# Demo.net
KiCad netlist of a schematic drawn in EAGLE
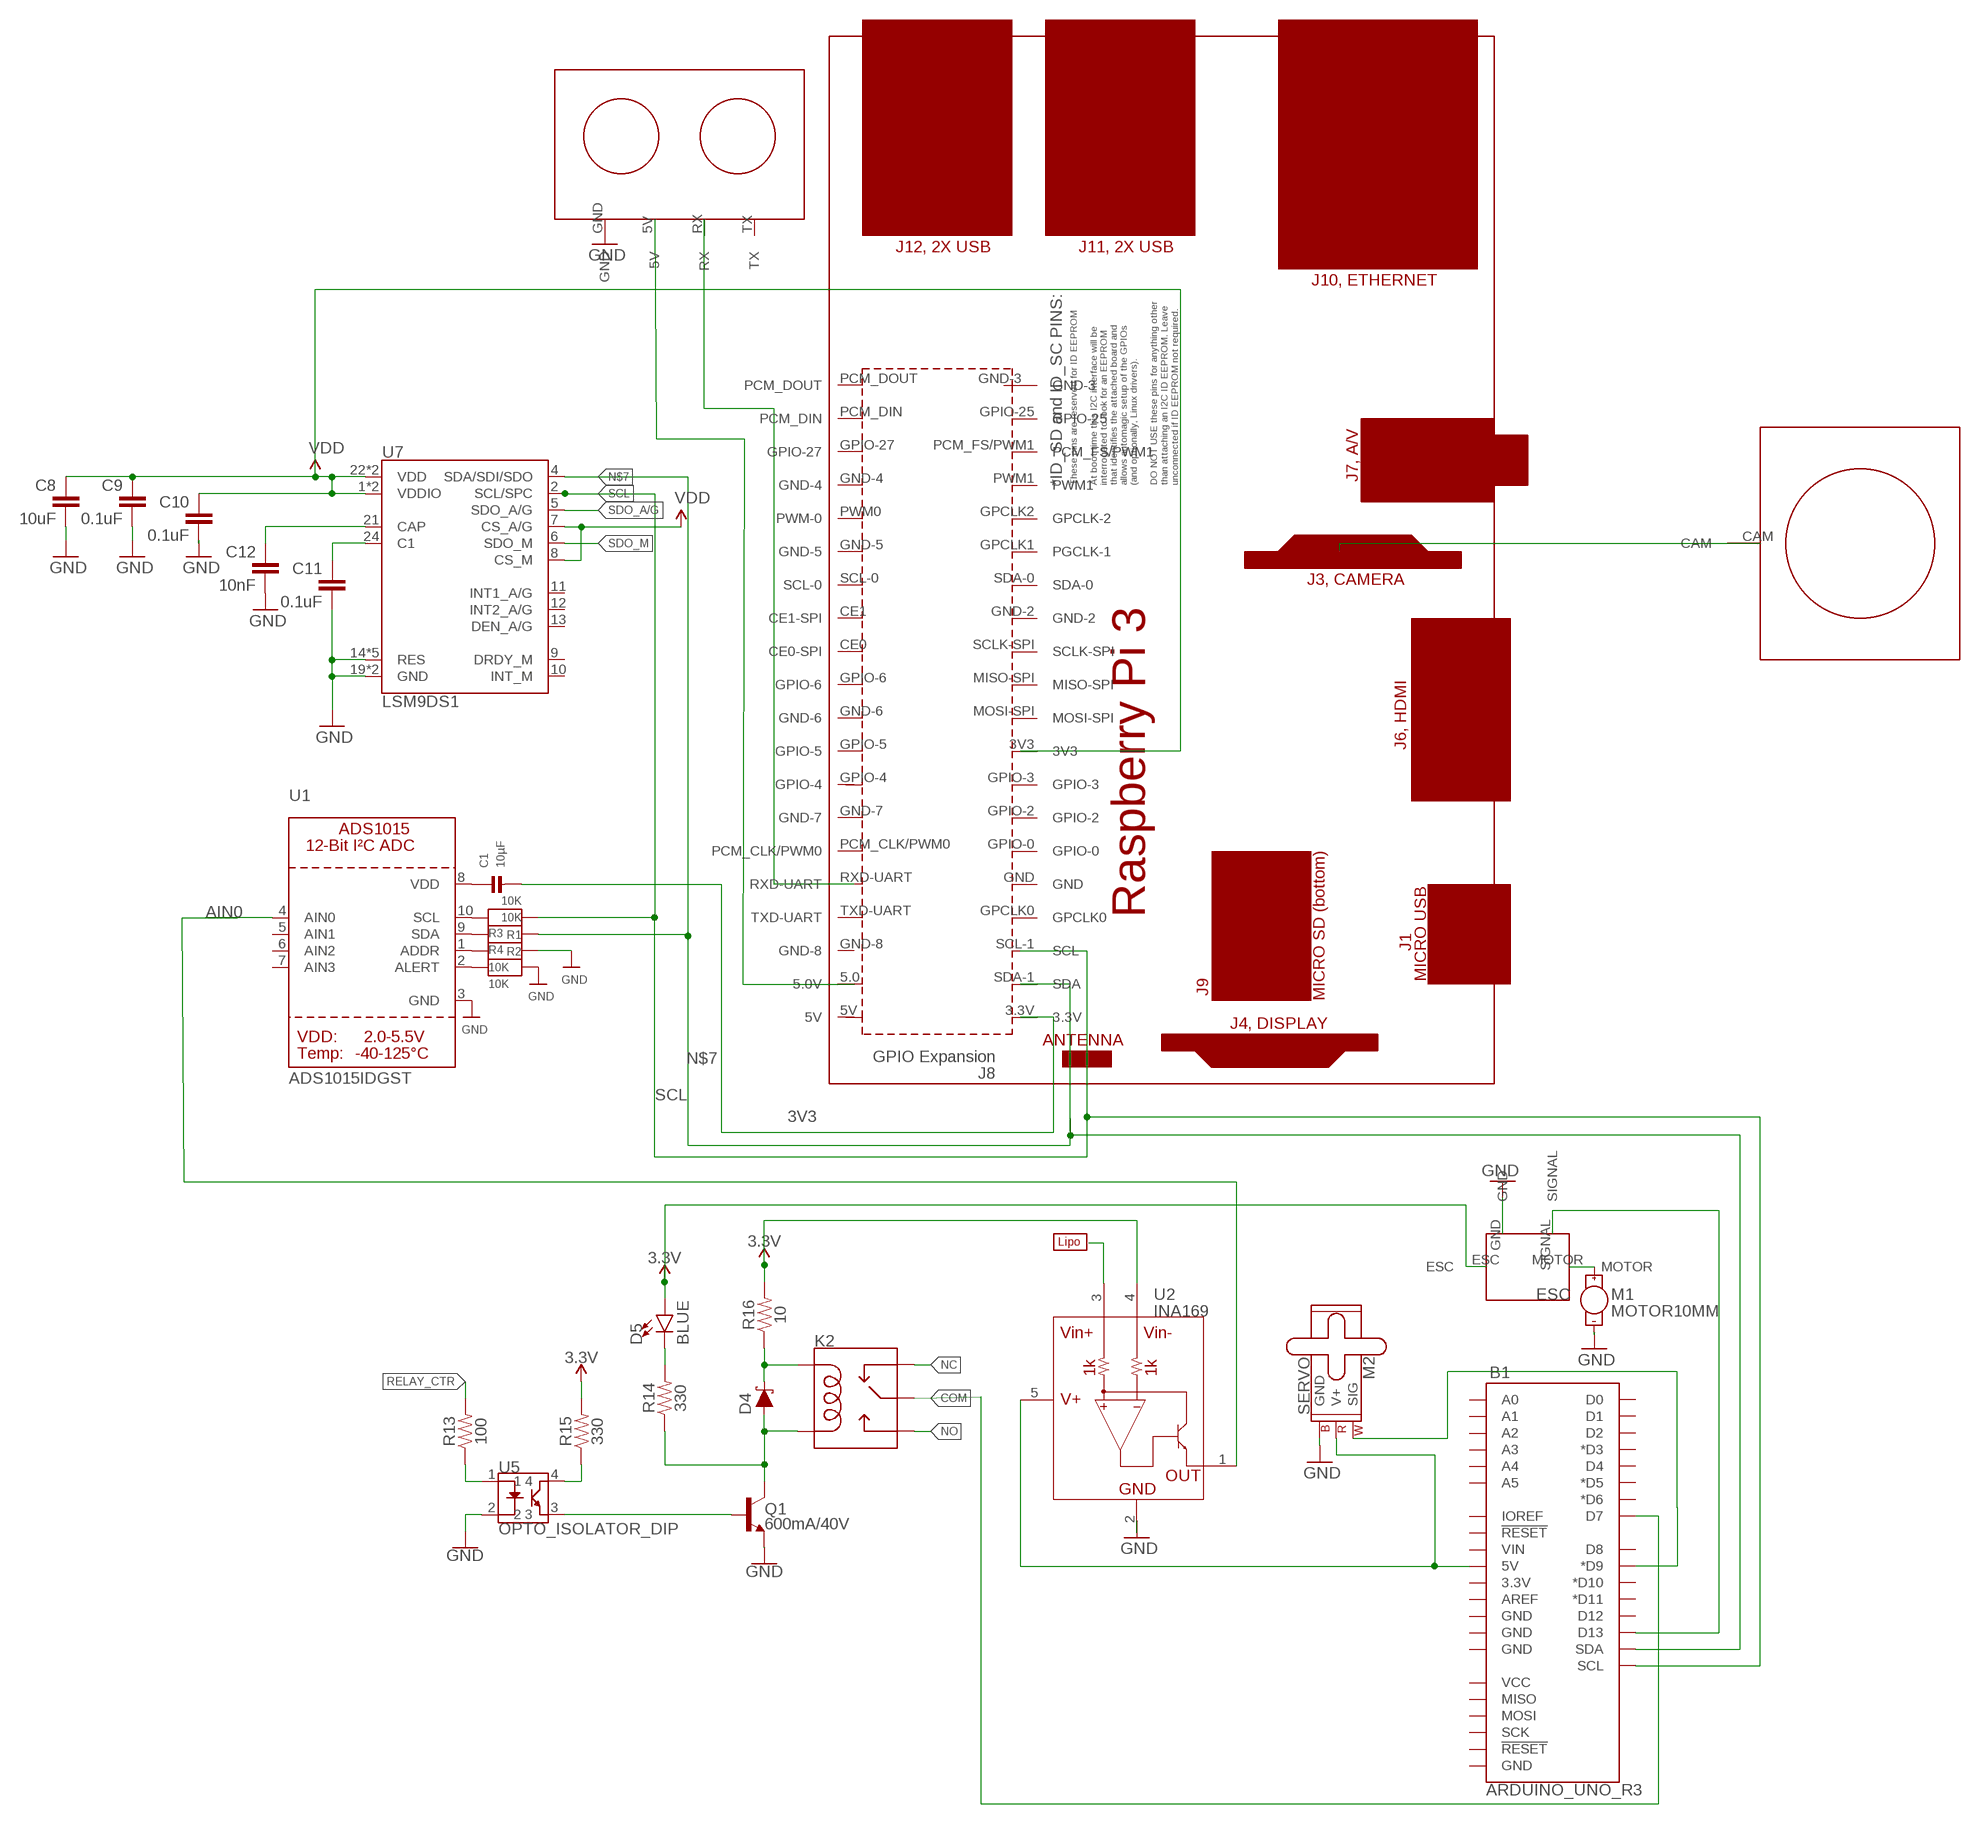
[diagram p0: schematic, sheet 1]

(export (version "E")
  (design (tool "Eeschema 10.0.6"))
  (components
    (comp (ref "B1")
      (value "ARDUINO_UNO_R3")
      (footprint "eagle-import:ARDUINO_R3")
      (libsource (lib "eagle-import") (part "ARDUINO_UNO_R3"))
    )
    (comp (ref "BT1")
      (value "LIPO-OUTLINE1100")
      (footprint "eagle-import:LIPO-1000")
      (libsource (lib "eagle-import") (part "LIPO-OUTLINE1100"))
    )
    (comp (ref "C1")
      (value "10µF")
      (footprint "eagle-import:0805")
      (libsource (lib "eagle-import") (part "CAP_CERAMIC0805"))
    )
    (comp (ref "C8")
      (value "10uF")
      (footprint "eagle-import:0603-CAP")
      (libsource (lib "eagle-import") (part "10UF-6.3V-20%(0603)"))
    )
    (comp (ref "C9")
      (value "0.1uF")
      (footprint "eagle-import:0603-CAP")
      (libsource (lib "eagle-import") (part "0.1UF-25V(+80/-20%)(0603)"))
    )
    (comp (ref "C10")
      (value "0.1uF")
      (footprint "eagle-import:0603-CAP")
      (libsource (lib "eagle-import") (part "0.1UF-25V(+80/-20%)(0603)"))
    )
    (comp (ref "C11")
      (value "0.1uF")
      (footprint "eagle-import:0603-CAP")
      (libsource (lib "eagle-import") (part "0.1UF-25V(+80/-20%)(0603)"))
    )
    (comp (ref "C12")
      (value "10nF")
      (footprint "eagle-import:0603-CAP")
      (libsource (lib "eagle-import") (part "10NF/10000PF-50V-10%(0603)"))
    )
    (comp (ref "D4")
      (value "1A/23V/620mV")
      (footprint "eagle-import:SOD-323")
      (libsource (lib "eagle-import") (part "DIODE-SCHOTTKY-BAT20J"))
    )
    (comp (ref "D5")
      (value "BLUE")
      (footprint "eagle-import:LED-0603")
      (libsource (lib "eagle-import") (part "LED-BLUE0603"))
    )
    (comp (ref "K2")
      (value "RELAY_SPDT_1C")
      (footprint "eagle-import:RELAY_SPDT_1C")
      (libsource (lib "eagle-import") (part "RELAY_SPDT_1C"))
    )
    (comp (ref "M1")
      (value "MOTOR10MM")
      (footprint "eagle-import:VIBE-MOTOR-10MM")
      (libsource (lib "eagle-import") (part "MOTOR10MM"))
    )
    (comp (ref "M2")
      (value "SERVO")
      (footprint "eagle-import:1X03")
      (libsource (lib "eagle-import") (part "SERVO"))
    )
    (comp (ref "Q1")
      (value "600mA/40V")
      (footprint "eagle-import:SOT23-3")
      (libsource (lib "eagle-import") (part "TRANS_NPN-MMBT2222AL"))
    )
    (comp (ref "R1")
      (value "10K")
      (footprint "eagle-import:0805")
      (libsource (lib "eagle-import") (part "RESISTOR0805"))
    )
    (comp (ref "R2")
      (value "10K")
      (footprint "eagle-import:0805")
      (libsource (lib "eagle-import") (part "RESISTOR0805"))
    )
    (comp (ref "R3")
      (value "10K")
      (footprint "eagle-import:0805")
      (libsource (lib "eagle-import") (part "RESISTOR0805"))
    )
    (comp (ref "R4")
      (value "10K")
      (footprint "eagle-import:0805")
      (libsource (lib "eagle-import") (part "RESISTOR0805"))
    )
    (comp (ref "R13")
      (value "100")
      (footprint "eagle-import:0603")
      (libsource (lib "eagle-import") (part "100OHM-0603-1/4W-5%"))
    )
    (comp (ref "R14")
      (value "330")
      (footprint "eagle-import:0603")
      (libsource (lib "eagle-import") (part "300OHM-0603-1/10W-1%"))
    )
    (comp (ref "R15")
      (value "330")
      (footprint "eagle-import:0603")
      (libsource (lib "eagle-import") (part "330OHM-0603-1/10W-1%"))
    )
    (comp (ref "R16")
      (value "10")
      (footprint "eagle-import:0603")
      (libsource (lib "eagle-import") (part "47KOHM-0603-1/10W-1%"))
    )
    (comp (ref "RPI1")
      (value "RPI3")
      (footprint "eagle-import:RPI")
      (libsource (lib "eagle-import") (part "RPI3"))
    )
    (comp (ref "U$1")
      (value "ESC")
      (footprint "eagle-import:ESC")
      (libsource (lib "eagle-import") (part "ESC"))
    )
    (comp (ref "U$3")
      (value "CAMERA")
      (footprint "eagle-import:CAMERA")
      (libsource (lib "eagle-import") (part "CAMERA"))
    )
    (comp (ref "U$4")
      (value "LIDAR")
      (footprint "eagle-import:LIDAR")
      (libsource (lib "eagle-import") (part "LIDAR"))
    )
    (comp (ref "U1")
      (value "ADS1015IDGST")
      (footprint "eagle-import:MSOP10")
      (libsource (lib "eagle-import") (part "ADC_ADS1015"))
    )
    (comp (ref "U2")
      (value "INA169")
      (footprint "eagle-import:SOT23-5")
      (libsource (lib "eagle-import") (part "INA169"))
    )
    (comp (ref "U5")
      (value "OPTO_ISOLATOR_DIP")
      (footprint "eagle-import:4PIN_DIP")
      (libsource (lib "eagle-import") (part "OPTO_ISOLATOR_DIP"))
    )
    (comp (ref "U7")
      (value "LSM9DS1")
      (footprint "eagle-import:LGA24-8X4")
      (libsource (lib "eagle-import") (part "LSM9DS1"))
    )
  )
  (nets
    (net (code "1") (name "/3V3") (class "Default")
      (node (ref "C1") (pin "2") (pinfunction "P$2_2") (pintype "passive"))
      (node (ref "RPI1") (pin "3.3V") (pinfunction "3.3V_3.3V") (pintype "power_in"))
    )
    (net (code "2") (name "/AIN0") (class "Default")
      (node (ref "U1") (pin "4") (pinfunction "AIN0_4") (pintype "bidirectional"))
      (node (ref "U2") (pin "1") (pinfunction "OUT_1") (pintype "bidirectional"))
    )
    (net (code "3") (name "3.3V") (class "Default")
      (node (ref "D5") (pin "A") (pinfunction "A_A") (pintype "passive"))
      (node (ref "R15") (pin "2") (pinfunction "2_2") (pintype "passive"))
      (node (ref "R16") (pin "2") (pinfunction "2_2") (pintype "passive"))
      (node (ref "U$1") (pin "ESC") (pinfunction "ESC_ESC") (pintype "power_in"))
      (node (ref "U2") (pin "4") (pinfunction "VIN-_4") (pintype "bidirectional"))
    )
    (net (code "4") (name "COM") (class "Default")
      (node (ref "B1") (pin "D7") (pinfunction "D7_D7") (pintype "bidirectional"))
      (node (ref "K2") (pin "1") (pinfunction "MAIN_1") (pintype "bidirectional"))
    )
    (net (code "5") (name "GND") (class "Default")
      (node (ref "C10") (pin "2") (pinfunction "2_2") (pintype "passive"))
      (node (ref "C11") (pin "2") (pinfunction "2_2") (pintype "passive"))
      (node (ref "C12") (pin "2") (pinfunction "2_2") (pintype "passive"))
      (node (ref "C8") (pin "2") (pinfunction "2_2") (pintype "passive"))
      (node (ref "C9") (pin "2") (pinfunction "2_2") (pintype "passive"))
      (node (ref "M1") (pin "-") (pinfunction "-_-") (pintype "bidirectional"))
      (node (ref "M2") (pin "3") (pinfunction "GND_3") (pintype "bidirectional"))
      (node (ref "Q1") (pin "2") (pinfunction "E_2") (pintype "passive"))
      (node (ref "R3") (pin "2") (pinfunction "2_2") (pintype "passive"))
      (node (ref "R4") (pin "2") (pinfunction "2_2") (pintype "passive"))
      (node (ref "U$1") (pin "GND") (pinfunction "GND_GND") (pintype "bidirectional"))
      (node (ref "U1") (pin "3") (pinfunction "GND_3") (pintype "bidirectional"))
      (node (ref "U2") (pin "2") (pinfunction "GND_2") (pintype "bidirectional"))
      (node (ref "U5") (pin "2") (pinfunction "2_2") (pintype "bidirectional"))
      (node (ref "U7") (pin "14") (pinfunction "RES_14") (pintype "bidirectional"))
      (node (ref "U7") (pin "15") (pinfunction "RES_15") (pintype "bidirectional"))
      (node (ref "U7") (pin "16") (pinfunction "RES_16") (pintype "bidirectional"))
      (node (ref "U7") (pin "17") (pinfunction "RES_17") (pintype "bidirectional"))
      (node (ref "U7") (pin "18") (pinfunction "RES_18") (pintype "bidirectional"))
      (node (ref "U7") (pin "19") (pinfunction "GND_19") (pintype "bidirectional"))
      (node (ref "U7") (pin "20") (pinfunction "GND_20") (pintype "bidirectional"))
    )
    (net (code "6") (name "N$7") (class "Default")
      (node (ref "B1") (pin "SDA") (pinfunction "SDA_SDA") (pintype "bidirectional"))
      (node (ref "R2") (pin "1") (pinfunction "1_1") (pintype "passive"))
      (node (ref "RPI1") (pin "SDA-1") (pinfunction "SDA_SDA-1") (pintype "bidirectional"))
      (node (ref "U7") (pin "4") (pinfunction "SDA/SDI/SDO_4") (pintype "bidirectional"))
    )
    (net (code "7") (name "NC") (class "Default")
      (node (ref "K2") (pin "4") (pinfunction "NC_4") (pintype "bidirectional"))
    )
    (net (code "8") (name "NO") (class "Default")
      (node (ref "K2") (pin "3") (pinfunction "NO_3") (pintype "bidirectional"))
    )
    (net (code "9") (name "Net-(B1-*D9)") (class "Default")
      (node (ref "B1") (pin "D9") (pinfunction "*D9_D9") (pintype "bidirectional"))
      (node (ref "M2") (pin "1") (pinfunction "SIG_1") (pintype "bidirectional"))
    )
    (net (code "10") (name "Net-(B1-PadD13)") (class "Default")
      (node (ref "B1") (pin "D13") (pinfunction "D13_D13") (pintype "bidirectional"))
      (node (ref "U$1") (pin "SIGNAL") (pinfunction "SIGNAL_SIGNAL") (pintype "bidirectional"))
    )
    (net (code "11") (name "Net-(C1-P$1)") (class "Default")
      (node (ref "C1") (pin "1") (pinfunction "P$1_1") (pintype "passive"))
      (node (ref "U1") (pin "8") (pinfunction "VDD_8") (pintype "bidirectional"))
    )
    (net (code "12") (name "Net-(D5-PadC)") (class "Default")
      (node (ref "D5") (pin "C") (pinfunction "C_C") (pintype "passive"))
      (node (ref "R14") (pin "2") (pinfunction "2_2") (pintype "passive"))
    )
    (net (code "13") (name "Net-(K2-COIL1)") (class "Default")
      (node (ref "D4") (pin "C") (pinfunction "C_C") (pintype "passive"))
      (node (ref "K2") (pin "2") (pinfunction "COIL1_2") (pintype "bidirectional"))
      (node (ref "R16") (pin "1") (pinfunction "1_1") (pintype "passive"))
    )
    (net (code "14") (name "Net-(K2-COIL2)") (class "Default")
      (node (ref "D4") (pin "A") (pinfunction "A_A") (pintype "passive"))
      (node (ref "K2") (pin "5") (pinfunction "COIL2_5") (pintype "bidirectional"))
      (node (ref "Q1") (pin "3") (pinfunction "C_3") (pintype "passive"))
      (node (ref "R14") (pin "1") (pinfunction "1_1") (pintype "passive"))
    )
    (net (code "15") (name "Net-(M1-Pad+)") (class "Default")
      (node (ref "M1") (pin "+") (pinfunction "+_+") (pintype "bidirectional"))
      (node (ref "U$1") (pin "MOTOR") (pinfunction "MOTOR_MOTOR") (pintype "bidirectional"))
    )
    (net (code "16") (name "Net-(M2-V+)") (class "Default")
      (node (ref "B1") (pin "5V") (pinfunction "5V_5V") (pintype "bidirectional"))
      (node (ref "M2") (pin "2") (pinfunction "V+_2") (pintype "bidirectional"))
      (node (ref "U2") (pin "5") (pinfunction "V+_5") (pintype "bidirectional"))
    )
    (net (code "17") (name "Net-(Q1-B)") (class "Default")
      (node (ref "Q1") (pin "1") (pinfunction "B_1") (pintype "passive"))
      (node (ref "U5") (pin "3") (pinfunction "3_3") (pintype "bidirectional"))
    )
    (net (code "18") (name "Net-(R13-Pad1)") (class "Default")
      (node (ref "R13") (pin "1") (pinfunction "1_1") (pintype "passive"))
      (node (ref "U5") (pin "1") (pinfunction "1_1") (pintype "bidirectional"))
    )
    (net (code "19") (name "Net-(R15-Pad1)") (class "Default")
      (node (ref "R15") (pin "1") (pinfunction "1_1") (pintype "passive"))
      (node (ref "U5") (pin "4") (pinfunction "4_4") (pintype "bidirectional"))
    )
    (net (code "20") (name "Net-(RPI1-5.0V)") (class "Default")
      (node (ref "RPI1") (pin "5.0") (pinfunction "5.0V_5.0") (pintype "bidirectional"))
      (node (ref "U$4") (pin "5V") (pinfunction "5V_5V") (pintype "power_in"))
    )
    (net (code "21") (name "Net-(RPI1-PadRXD-UART)") (class "Default")
      (node (ref "RPI1") (pin "RXD-UART") (pinfunction "RXD-UART_RXD-UART") (pintype "bidirectional"))
      (node (ref "U$4") (pin "RX") (pinfunction "RX_RX") (pintype "bidirectional"))
    )
    (net (code "22") (name "Net-(U1-ADDR)") (class "Default")
      (node (ref "R3") (pin "1") (pinfunction "1_1") (pintype "passive"))
      (node (ref "U1") (pin "1") (pinfunction "ADDR_1") (pintype "bidirectional"))
    )
    (net (code "23") (name "Net-(U1-ALERT)") (class "Default")
      (node (ref "R4") (pin "1") (pinfunction "1_1") (pintype "passive"))
      (node (ref "U1") (pin "2") (pinfunction "ALERT_2") (pintype "bidirectional"))
    )
    (net (code "24") (name "Net-(U1-SCL)") (class "Default")
      (node (ref "R1") (pin "2") (pinfunction "2_2") (pintype "passive"))
      (node (ref "U1") (pin "10") (pinfunction "SCL_10") (pintype "bidirectional"))
    )
    (net (code "25") (name "Net-(U1-SDA)") (class "Default")
      (node (ref "R2") (pin "2") (pinfunction "2_2") (pintype "passive"))
      (node (ref "U1") (pin "9") (pinfunction "SDA_9") (pintype "bidirectional"))
    )
    (net (code "26") (name "Net-(U7-C1)") (class "Default")
      (node (ref "C11") (pin "1") (pinfunction "1_1") (pintype "passive"))
      (node (ref "U7") (pin "24") (pinfunction "C1_24") (pintype "bidirectional"))
    )
    (net (code "27") (name "Net-(U7-CAP)") (class "Default")
      (node (ref "C12") (pin "1") (pinfunction "1_1") (pintype "passive"))
      (node (ref "U7") (pin "21") (pinfunction "CAP_21") (pintype "bidirectional"))
    )
    (net (code "28") (name "RELAY_CTR") (class "Default")
      (node (ref "R13") (pin "2") (pinfunction "2_2") (pintype "passive"))
    )
    (net (code "29") (name "SCL") (class "Default")
      (node (ref "B1") (pin "SCL") (pinfunction "SCL_SCL") (pintype "bidirectional"))
      (node (ref "R1") (pin "1") (pinfunction "1_1") (pintype "passive"))
      (node (ref "RPI1") (pin "SCL-1") (pinfunction "SCL_SCL-1") (pintype "bidirectional"))
      (node (ref "U7") (pin "2") (pinfunction "SCL/SPC_2") (pintype "bidirectional"))
    )
    (net (code "30") (name "SDO_A{slash}G") (class "Default")
      (node (ref "U7") (pin "5") (pinfunction "SDO_A/G_5") (pintype "bidirectional"))
    )
    (net (code "31") (name "SDO_M") (class "Default")
      (node (ref "U7") (pin "6") (pinfunction "SDO_M_6") (pintype "bidirectional"))
    )
    (net (code "32") (name "VDD") (class "Default")
      (node (ref "C10") (pin "1") (pinfunction "1_1") (pintype "passive"))
      (node (ref "C8") (pin "1") (pinfunction "1_1") (pintype "passive"))
      (node (ref "C9") (pin "1") (pinfunction "1_1") (pintype "passive"))
      (node (ref "RPI1") (pin "3V3") (pinfunction "3V3_3V3") (pintype "power_in"))
      (node (ref "U7") (pin "1") (pinfunction "VDDIO_1") (pintype "bidirectional"))
      (node (ref "U7") (pin "22") (pinfunction "VDD_22") (pintype "bidirectional"))
      (node (ref "U7") (pin "23") (pinfunction "VDD_23") (pintype "bidirectional"))
      (node (ref "U7") (pin "3") (pinfunction "VDDIO_3") (pintype "bidirectional"))
      (node (ref "U7") (pin "7") (pinfunction "CS_A/G_7") (pintype "bidirectional"))
      (node (ref "U7") (pin "8") (pinfunction "CS_M_8") (pintype "bidirectional"))
    )
    (net (code "33") (name "unconnected-(B1-*D3-PadD3)") (class "Default")
      (node (ref "B1") (pin "D3") (pinfunction "*D3_D3") (pintype "bidirectional"))
    )
    (net (code "34") (name "unconnected-(B1-*D5-PadD5)") (class "Default")
      (node (ref "B1") (pin "D5") (pinfunction "*D5_D5") (pintype "bidirectional"))
    )
    (net (code "35") (name "unconnected-(B1-*D6-PadD6)") (class "Default")
      (node (ref "B1") (pin "D6") (pinfunction "*D6_D6") (pintype "bidirectional"))
    )
    (net (code "36") (name "unconnected-(B1-*D10-PadD10)") (class "Default")
      (node (ref "B1") (pin "D10") (pinfunction "*D10_D10") (pintype "bidirectional"))
    )
    (net (code "37") (name "unconnected-(B1-*D11-PadD11)") (class "Default")
      (node (ref "B1") (pin "D11") (pinfunction "*D11_D11") (pintype "bidirectional"))
    )
    (net (code "38") (name "unconnected-(B1-GND-PadGND@1)") (class "Default")
      (node (ref "B1") (pin "GND@1") (pinfunction "GND_GND@1") (pintype "bidirectional"))
    )
    (net (code "39") (name "unconnected-(B1-GND-PadGND@2)") (class "Default")
      (node (ref "B1") (pin "GND@2") (pinfunction "GND_GND@2") (pintype "bidirectional"))
    )
    (net (code "40") (name "unconnected-(B1-GND-PadGND@3)") (class "Default")
      (node (ref "B1") (pin "GND@3") (pinfunction "GND_GND@3") (pintype "bidirectional"))
    )
    (net (code "41") (name "unconnected-(B1-GND-PadGND@4)") (class "Default")
      (node (ref "B1") (pin "GND@4") (pinfunction "GND_GND@4") (pintype "bidirectional"))
    )
    (net (code "42") (name "unconnected-(B1-Pad3.3V)") (class "Default")
      (node (ref "B1") (pin "3.3V") (pinfunction "3.3V_3.3V") (pintype "bidirectional"))
    )
    (net (code "43") (name "unconnected-(B1-PadA0)") (class "Default")
      (node (ref "B1") (pin "A0") (pinfunction "A0_A0") (pintype "bidirectional"))
    )
    (net (code "44") (name "unconnected-(B1-PadA1)") (class "Default")
      (node (ref "B1") (pin "A1") (pinfunction "A1_A1") (pintype "bidirectional"))
    )
    (net (code "45") (name "unconnected-(B1-PadA2)") (class "Default")
      (node (ref "B1") (pin "A2") (pinfunction "A2_A2") (pintype "bidirectional"))
    )
    (net (code "46") (name "unconnected-(B1-PadA3)") (class "Default")
      (node (ref "B1") (pin "A3") (pinfunction "A3_A3") (pintype "bidirectional"))
    )
    (net (code "47") (name "unconnected-(B1-PadA4)") (class "Default")
      (node (ref "B1") (pin "A4") (pinfunction "A4_A4") (pintype "bidirectional"))
    )
    (net (code "48") (name "unconnected-(B1-PadA5)") (class "Default")
      (node (ref "B1") (pin "A5") (pinfunction "A5_A5") (pintype "bidirectional"))
    )
    (net (code "49") (name "unconnected-(B1-PadAREF)") (class "Default")
      (node (ref "B1") (pin "AREF") (pinfunction "AREF_AREF") (pintype "bidirectional"))
    )
    (net (code "50") (name "unconnected-(B1-PadD0)") (class "Default")
      (node (ref "B1") (pin "D0") (pinfunction "D0_D0") (pintype "bidirectional"))
    )
    (net (code "51") (name "unconnected-(B1-PadD1)") (class "Default")
      (node (ref "B1") (pin "D1") (pinfunction "D1_D1") (pintype "bidirectional"))
    )
    (net (code "52") (name "unconnected-(B1-PadD2)") (class "Default")
      (node (ref "B1") (pin "D2") (pinfunction "D2_D2") (pintype "bidirectional"))
    )
    (net (code "53") (name "unconnected-(B1-PadD4)") (class "Default")
      (node (ref "B1") (pin "D4") (pinfunction "D4_D4") (pintype "bidirectional"))
    )
    (net (code "54") (name "unconnected-(B1-PadD8)") (class "Default")
      (node (ref "B1") (pin "D8") (pinfunction "D8_D8") (pintype "bidirectional"))
    )
    (net (code "55") (name "unconnected-(B1-PadD12)") (class "Default")
      (node (ref "B1") (pin "D12") (pinfunction "D12_D12") (pintype "bidirectional"))
    )
    (net (code "56") (name "unconnected-(B1-PadIOREF)") (class "Default")
      (node (ref "B1") (pin "IOREF") (pinfunction "IOREF_IOREF") (pintype "bidirectional"))
    )
    (net (code "57") (name "unconnected-(B1-PadMISO)") (class "Default")
      (node (ref "B1") (pin "MISO") (pinfunction "MISO_MISO") (pintype "bidirectional"))
    )
    (net (code "58") (name "unconnected-(B1-PadMOSI)") (class "Default")
      (node (ref "B1") (pin "MOSI") (pinfunction "MOSI_MOSI") (pintype "bidirectional"))
    )
    (net (code "59") (name "unconnected-(B1-PadSCK)") (class "Default")
      (node (ref "B1") (pin "SCK") (pinfunction "SCK_SCK") (pintype "bidirectional"))
    )
    (net (code "60") (name "unconnected-(B1-PadVCC)") (class "Default")
      (node (ref "B1") (pin "VCC") (pinfunction "VCC_VCC") (pintype "bidirectional"))
    )
    (net (code "61") (name "unconnected-(B1-PadVIN)") (class "Default")
      (node (ref "B1") (pin "VIN") (pinfunction "VIN_VIN") (pintype "bidirectional"))
    )
    (net (code "62") (name "unconnected-(B1-~{RESET}-PadRESET@1)") (class "Default")
      (node (ref "B1") (pin "RESET@1") (pinfunction "~{RESET}_RESET@1") (pintype "bidirectional"))
    )
    (net (code "63") (name "unconnected-(B1-~{RESET}-PadRESET@2)") (class "Default")
      (node (ref "B1") (pin "RESET@2") (pinfunction "~{RESET}_RESET@2") (pintype "bidirectional"))
    )
    (net (code "64") (name "unconnected-(RPI1-CE0-SPI-PadCE0)") (class "Default")
      (node (ref "RPI1") (pin "CE0") (pinfunction "CE0-SPI_CE0") (pintype "bidirectional"))
    )
    (net (code "65") (name "unconnected-(RPI1-CE1-SPI-PadCE1)") (class "Default")
      (node (ref "RPI1") (pin "CE1") (pinfunction "CE1-SPI_CE1") (pintype "bidirectional"))
    )
    (net (code "66") (name "unconnected-(RPI1-GPCLK-2-PadGPCLK2)") (class "Default")
      (node (ref "RPI1") (pin "GPCLK2") (pinfunction "GPCLK-2_GPCLK2") (pintype "bidirectional"))
    )
    (net (code "67") (name "unconnected-(RPI1-PGCLK-1-PadGPCLK1)") (class "Default")
      (node (ref "RPI1") (pin "GPCLK1") (pinfunction "PGCLK-1_GPCLK1") (pintype "bidirectional"))
    )
    (net (code "68") (name "unconnected-(RPI1-PWM-0-PadPWM0)") (class "Default")
      (node (ref "RPI1") (pin "PWM0") (pinfunction "PWM-0_PWM0") (pintype "bidirectional"))
    )
    (net (code "69") (name "unconnected-(RPI1-Pad5V)") (class "Default")
      (node (ref "RPI1") (pin "5V") (pinfunction "5V_5V") (pintype "bidirectional"))
    )
    (net (code "70") (name "unconnected-(RPI1-PadGND)") (class "Default")
      (node (ref "RPI1") (pin "GND") (pinfunction "GND_GND") (pintype "bidirectional"))
    )
    (net (code "71") (name "unconnected-(RPI1-PadGND-2)") (class "Default")
      (node (ref "RPI1") (pin "GND-2") (pinfunction "GND-2_GND-2") (pintype "bidirectional"))
    )
    (net (code "72") (name "unconnected-(RPI1-PadGND-3)") (class "Default")
      (node (ref "RPI1") (pin "GND-3") (pinfunction "GND-3_GND-3") (pintype "bidirectional"))
    )
    (net (code "73") (name "unconnected-(RPI1-PadGND-4)") (class "Default")
      (node (ref "RPI1") (pin "GND-4") (pinfunction "GND-4_GND-4") (pintype "bidirectional"))
    )
    (net (code "74") (name "unconnected-(RPI1-PadGND-5)") (class "Default")
      (node (ref "RPI1") (pin "GND-5") (pinfunction "GND-5_GND-5") (pintype "bidirectional"))
    )
    (net (code "75") (name "unconnected-(RPI1-PadGND-6)") (class "Default")
      (node (ref "RPI1") (pin "GND-6") (pinfunction "GND-6_GND-6") (pintype "bidirectional"))
    )
    (net (code "76") (name "unconnected-(RPI1-PadGND-7)") (class "Default")
      (node (ref "RPI1") (pin "GND-7") (pinfunction "GND-7_GND-7") (pintype "bidirectional"))
    )
    (net (code "77") (name "unconnected-(RPI1-PadGND-8)") (class "Default")
      (node (ref "RPI1") (pin "GND-8") (pinfunction "GND-8_GND-8") (pintype "bidirectional"))
    )
    (net (code "78") (name "unconnected-(RPI1-PadGPCLK0)") (class "Default")
      (node (ref "RPI1") (pin "GPCLK0") (pinfunction "GPCLK0_GPCLK0") (pintype "bidirectional"))
    )
    (net (code "79") (name "unconnected-(RPI1-PadGPIO-0)") (class "Default")
      (node (ref "RPI1") (pin "GPIO-0") (pinfunction "GPIO-0_GPIO-0") (pintype "bidirectional"))
    )
    (net (code "80") (name "unconnected-(RPI1-PadGPIO-2)") (class "Default")
      (node (ref "RPI1") (pin "GPIO-2") (pinfunction "GPIO-2_GPIO-2") (pintype "bidirectional"))
    )
    (net (code "81") (name "unconnected-(RPI1-PadGPIO-3)") (class "Default")
      (node (ref "RPI1") (pin "GPIO-3") (pinfunction "GPIO-3_GPIO-3") (pintype "bidirectional"))
    )
    (net (code "82") (name "unconnected-(RPI1-PadGPIO-4)") (class "Default")
      (node (ref "RPI1") (pin "GPIO-4") (pinfunction "GPIO-4_GPIO-4") (pintype "bidirectional"))
    )
    (net (code "83") (name "unconnected-(RPI1-PadGPIO-5)") (class "Default")
      (node (ref "RPI1") (pin "GPIO-5") (pinfunction "GPIO-5_GPIO-5") (pintype "bidirectional"))
    )
    (net (code "84") (name "unconnected-(RPI1-PadGPIO-6)") (class "Default")
      (node (ref "RPI1") (pin "GPIO-6") (pinfunction "GPIO-6_GPIO-6") (pintype "bidirectional"))
    )
    (net (code "85") (name "unconnected-(RPI1-PadGPIO-25)") (class "Default")
      (node (ref "RPI1") (pin "GPIO-25") (pinfunction "GPIO-25_GPIO-25") (pintype "bidirectional"))
    )
    (net (code "86") (name "unconnected-(RPI1-PadGPIO-27)") (class "Default")
      (node (ref "RPI1") (pin "GPIO-27") (pinfunction "GPIO-27_GPIO-27") (pintype "bidirectional"))
    )
    (net (code "87") (name "unconnected-(RPI1-PadMISO-SPI)") (class "Default")
      (node (ref "RPI1") (pin "MISO-SPI") (pinfunction "MISO-SPI_MISO-SPI") (pintype "bidirectional"))
    )
    (net (code "88") (name "unconnected-(RPI1-PadMOSI-SPI)") (class "Default")
      (node (ref "RPI1") (pin "MOSI-SPI") (pinfunction "MOSI-SPI_MOSI-SPI") (pintype "bidirectional"))
    )
    (net (code "89") (name "unconnected-(RPI1-PadPCM_CLK{slash}PWM0)") (class "Default")
      (node (ref "RPI1") (pin "PCM_CLK/PWM0") (pinfunction "PCM_CLK/PWM0_PCM_CLK/PWM0") (pintype "bidirectional"))
    )
    (net (code "90") (name "unconnected-(RPI1-PadPCM_DIN)") (class "Default")
      (node (ref "RPI1") (pin "PCM_DIN") (pinfunction "PCM_DIN_PCM_DIN") (pintype "bidirectional"))
    )
    (net (code "91") (name "unconnected-(RPI1-PadPCM_DOUT)") (class "Default")
      (node (ref "RPI1") (pin "PCM_DOUT") (pinfunction "PCM_DOUT_PCM_DOUT") (pintype "bidirectional"))
    )
    (net (code "92") (name "unconnected-(RPI1-PadPCM_FS{slash}PWM1)") (class "Default")
      (node (ref "RPI1") (pin "PCM_FS/PWM1") (pinfunction "PCM_FS/PWM1_PCM_FS/PWM1") (pintype "bidirectional"))
    )
    (net (code "93") (name "unconnected-(RPI1-PadPWM1)") (class "Default")
      (node (ref "RPI1") (pin "PWM1") (pinfunction "PWM1_PWM1") (pintype "bidirectional"))
    )
    (net (code "94") (name "unconnected-(RPI1-PadSCL-0)") (class "Default")
      (node (ref "RPI1") (pin "SCL-0") (pinfunction "SCL-0_SCL-0") (pintype "bidirectional"))
    )
    (net (code "95") (name "unconnected-(RPI1-PadSCLK-SPI)") (class "Default")
      (node (ref "RPI1") (pin "SCLK-SPI") (pinfunction "SCLK-SPI_SCLK-SPI") (pintype "bidirectional"))
    )
    (net (code "96") (name "unconnected-(RPI1-PadSDA-0)") (class "Default")
      (node (ref "RPI1") (pin "SDA-0") (pinfunction "SDA-0_SDA-0") (pintype "bidirectional"))
    )
    (net (code "97") (name "unconnected-(RPI1-PadTXD-UART)") (class "Default")
      (node (ref "RPI1") (pin "TXD-UART") (pinfunction "TXD-UART_TXD-UART") (pintype "bidirectional"))
    )
    (net (code "98") (name "unconnected-(U$3-PadCAM)") (class "Default")
      (node (ref "U$3") (pin "CAM") (pinfunction "CAM_CAM") (pintype "bidirectional"))
    )
    (net (code "99") (name "unconnected-(U$4-PadGND)") (class "Default")
      (node (ref "U$4") (pin "GND") (pinfunction "GND_GND") (pintype "bidirectional"))
    )
    (net (code "100") (name "unconnected-(U$4-PadTX)") (class "Default")
      (node (ref "U$4") (pin "TX") (pinfunction "TX_TX") (pintype "bidirectional"))
    )
    (net (code "101") (name "unconnected-(U1-AIN1-Pad5)") (class "Default")
      (node (ref "U1") (pin "5") (pinfunction "AIN1_5") (pintype "bidirectional"))
    )
    (net (code "102") (name "unconnected-(U1-AIN2-Pad6)") (class "Default")
      (node (ref "U1") (pin "6") (pinfunction "AIN2_6") (pintype "bidirectional"))
    )
    (net (code "103") (name "unconnected-(U1-AIN3-Pad7)") (class "Default")
      (node (ref "U1") (pin "7") (pinfunction "AIN3_7") (pintype "bidirectional"))
    )
    (net (code "104") (name "unconnected-(U2-VIN+-Pad3)") (class "Default")
      (node (ref "U2") (pin "3") (pinfunction "VIN+_3") (pintype "bidirectional"))
    )
    (net (code "105") (name "unconnected-(U7-DEN_A{slash}G-Pad13)") (class "Default")
      (node (ref "U7") (pin "13") (pinfunction "DEN_A/G_13") (pintype "bidirectional"))
    )
    (net (code "106") (name "unconnected-(U7-DRDY_M-Pad9)") (class "Default")
      (node (ref "U7") (pin "9") (pinfunction "DRDY_M_9") (pintype "bidirectional"))
    )
    (net (code "107") (name "unconnected-(U7-INT1_A{slash}G-Pad11)") (class "Default")
      (node (ref "U7") (pin "11") (pinfunction "INT1_A/G_11") (pintype "bidirectional"))
    )
    (net (code "108") (name "unconnected-(U7-INT2_A{slash}G-Pad12)") (class "Default")
      (node (ref "U7") (pin "12") (pinfunction "INT2_A/G_12") (pintype "bidirectional"))
    )
    (net (code "109") (name "unconnected-(U7-INT_M-Pad10)") (class "Default")
      (node (ref "U7") (pin "10") (pinfunction "INT_M_10") (pintype "bidirectional"))
    )
  )
)
